# Sheet1.net
KiCad netlist of a schematic drawn in Altium Designer
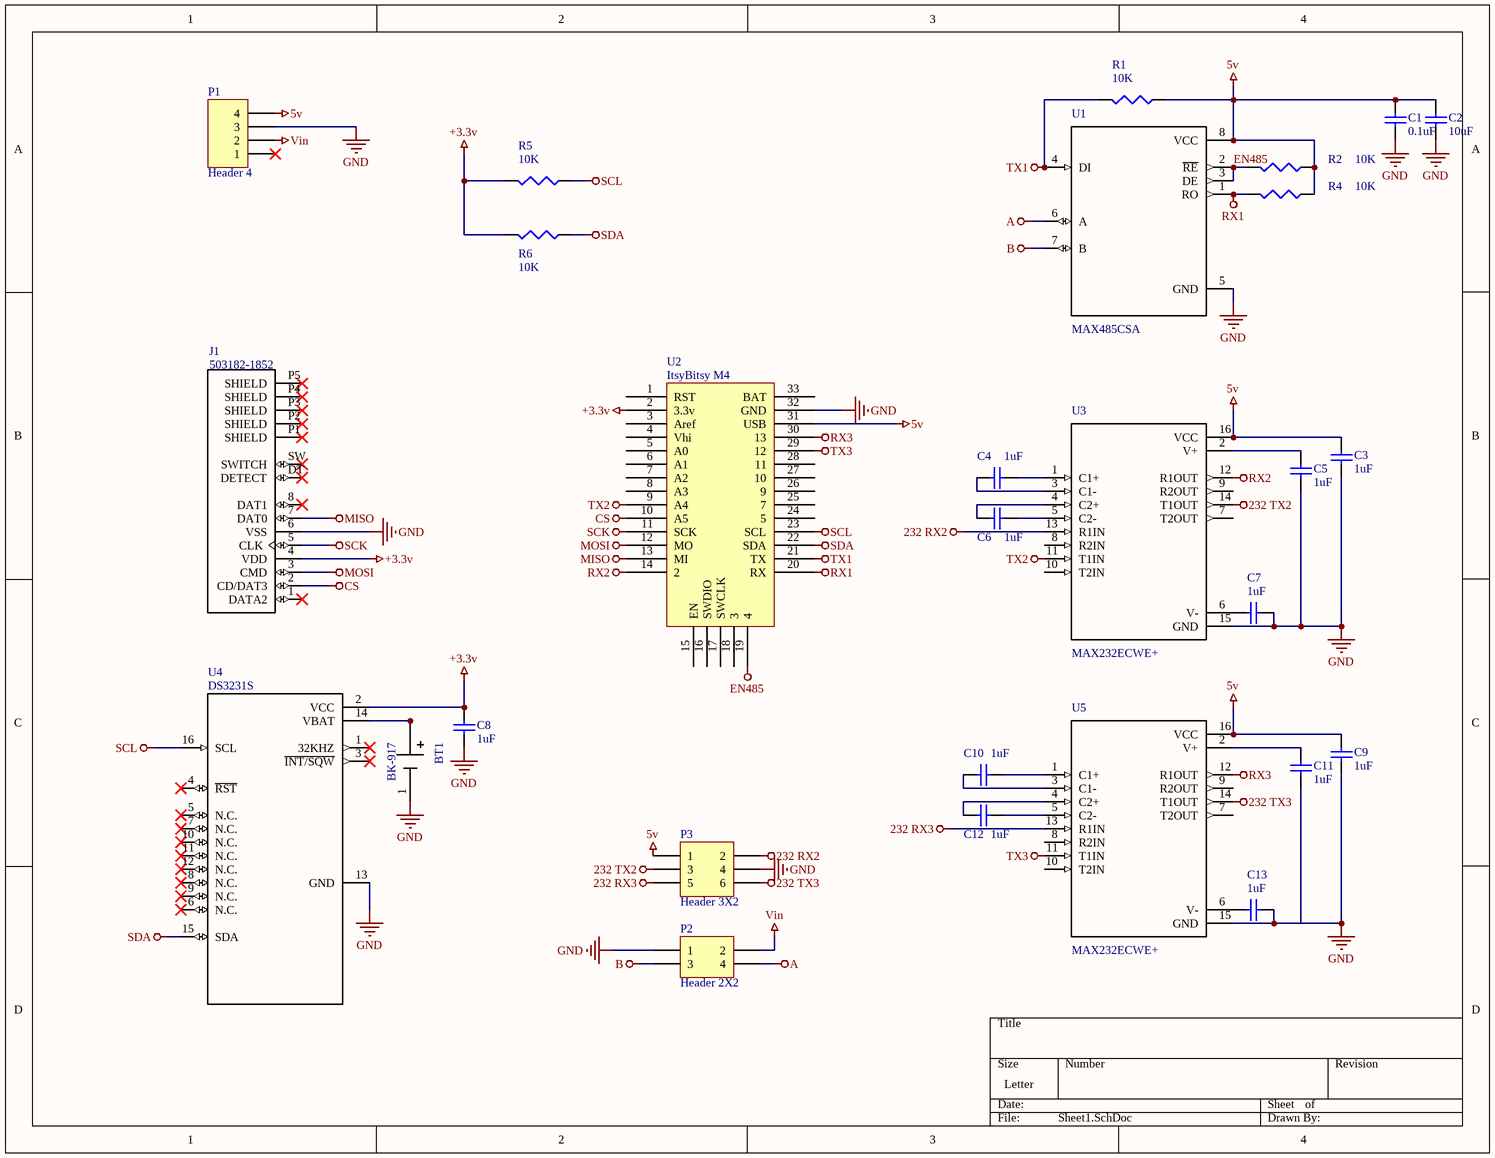
[diagram p0: Sheet1.SchDoc]

(export (version "E")
  (design (tool "Eeschema 10.0.6"))
  (components
    (comp (ref "BT1")
      (value "BK-917")
      (footprint "*BAT_BK-917_BK-917(Primary)")
      (description "BATTERY RETAINER COIN PC PIN")
      (fields (field (name "MF") "MPD"))
      (libsource (lib "BK-917") (part "BK-917"))
    )
    (comp (ref "C1")
      (value "0.1uF")
      (footprint "1608[0603]")
      (description "Capacitor (Semiconductor SIM Model)")
      (fields (field (name "Comment") "Cap Semi") (field (name "PUBLISHER") "Altium Limited"))
      (libsource (lib "Miscellaneous Devices") (part "Cap Semi"))
    )
    (comp (ref "C2")
      (value "10uF")
      (footprint "1608[0603]")
      (description "Capacitor (Semiconductor SIM Model)")
      (fields (field (name "Comment") "Cap Semi") (field (name "PUBLISHER") "Altium Limited"))
      (libsource (lib "Miscellaneous Devices") (part "Cap Semi"))
    )
    (comp (ref "C3")
      (value "1uF")
      (footprint "1608[0603]")
      (description "Capacitor (Semiconductor SIM Model)")
      (fields (field (name "Comment") "Cap Semi") (field (name "PUBLISHER") "Altium Limited"))
      (libsource (lib "Miscellaneous Devices") (part "Cap Semi"))
    )
    (comp (ref "C4")
      (value "1uF")
      (footprint "1608[0603]")
      (description "Capacitor (Semiconductor SIM Model)")
      (fields (field (name "Comment") "Cap Semi") (field (name "PUBLISHER") "Altium Limited"))
      (libsource (lib "Miscellaneous Devices") (part "Cap Semi"))
    )
    (comp (ref "C5")
      (value "1uF")
      (footprint "1608[0603]")
      (description "Capacitor (Semiconductor SIM Model)")
      (fields (field (name "Comment") "Cap Semi") (field (name "PUBLISHER") "Altium Limited"))
      (libsource (lib "Miscellaneous Devices") (part "Cap Semi"))
    )
    (comp (ref "C6")
      (value "1uF")
      (footprint "1608[0603]")
      (description "Capacitor (Semiconductor SIM Model)")
      (fields (field (name "Comment") "Cap Semi") (field (name "PUBLISHER") "Altium Limited"))
      (libsource (lib "Miscellaneous Devices") (part "Cap Semi"))
    )
    (comp (ref "C7")
      (value "1uF")
      (footprint "1608[0603]")
      (description "Capacitor (Semiconductor SIM Model)")
      (fields (field (name "Comment") "Cap Semi") (field (name "PUBLISHER") "Altium Limited"))
      (libsource (lib "Miscellaneous Devices") (part "Cap Semi"))
    )
    (comp (ref "C8")
      (value "1uF")
      (footprint "1608[0603]")
      (description "Capacitor (Semiconductor SIM Model)")
      (fields (field (name "Comment") "Cap Semi") (field (name "PUBLISHER") "Altium Limited"))
      (libsource (lib "Miscellaneous Devices") (part "Cap Semi"))
    )
    (comp (ref "C9")
      (value "1uF")
      (footprint "1608[0603]")
      (description "Capacitor (Semiconductor SIM Model)")
      (fields (field (name "Comment") "Cap Semi") (field (name "PUBLISHER") "Altium Limited"))
      (libsource (lib "Miscellaneous Devices") (part "Cap Semi"))
    )
    (comp (ref "C10")
      (value "1uF")
      (footprint "1608[0603]")
      (description "Capacitor (Semiconductor SIM Model)")
      (fields (field (name "Comment") "Cap Semi") (field (name "PUBLISHER") "Altium Limited"))
      (libsource (lib "Miscellaneous Devices") (part "Cap Semi"))
    )
    (comp (ref "C11")
      (value "1uF")
      (footprint "1608[0603]")
      (description "Capacitor (Semiconductor SIM Model)")
      (fields (field (name "Comment") "Cap Semi") (field (name "PUBLISHER") "Altium Limited"))
      (libsource (lib "Miscellaneous Devices") (part "Cap Semi"))
    )
    (comp (ref "C12")
      (value "1uF")
      (footprint "1608[0603]")
      (description "Capacitor (Semiconductor SIM Model)")
      (fields (field (name "Comment") "Cap Semi") (field (name "PUBLISHER") "Altium Limited"))
      (libsource (lib "Miscellaneous Devices") (part "Cap Semi"))
    )
    (comp (ref "C13")
      (value "1uF")
      (footprint "1608[0603]")
      (description "Capacitor (Semiconductor SIM Model)")
      (fields (field (name "Comment") "Cap Semi") (field (name "PUBLISHER") "Altium Limited"))
      (libsource (lib "Miscellaneous Devices") (part "Cap Semi"))
    )
    (comp (ref "J1")
      (value "503182-1852")
      (footprint "*MOLEX_503182-1852_503182-1852(Primary)")
      (description "MICRO SD NORMAL ULTRALOWPRO8CKTE")
      (fields (field (name "MP") "5031821852") (field (name "MF") "Molex"))
      (libsource (lib "503182-1852") (part "503182-1852"))
    )
    (comp (ref "P1")
      (value "Header 4")
      (footprint "HDR1X4")
      (description "Header, 4-Pin")
      (fields (field (name "PUBLISHER") "Altium Limited"))
      (libsource (lib "Miscellaneous Connectors") (part "Header 4"))
    )
    (comp (ref "P2")
      (value "Header 2X2")
      (footprint "2x2 MOLEX")
      (description "Header, 2-Pin, Dual row")
      (fields (field (name "PUBLISHER") "Altium Limited"))
      (libsource (lib "Miscellaneous Connectors") (part "Header 2X2"))
    )
    (comp (ref "P3")
      (value "Header 3X2")
      (footprint "2x3 MOLEX")
      (description "Header, 3-Pin, Dual row")
      (fields (field (name "PUBLISHER") "Altium Limited"))
      (libsource (lib "Miscellaneous Connectors") (part "Header 3X2"))
    )
    (comp (ref "R1")
      (value "10K")
      (footprint "J1-0603")
      (description "Resistor")
      (fields (field (name "Comment") "Res3") (field (name "PUBLISHER") "Altium Limited"))
      (libsource (lib "Miscellaneous Devices") (part "Res3"))
    )
    (comp (ref "R2")
      (value "10K")
      (footprint "J1-0603")
      (description "Resistor")
      (fields (field (name "Comment") "Res3") (field (name "PUBLISHER") "Altium Limited"))
      (libsource (lib "Miscellaneous Devices") (part "Res3"))
    )
    (comp (ref "R4")
      (value "10K")
      (footprint "J1-0603")
      (description "Resistor")
      (fields (field (name "Comment") "Res3") (field (name "PUBLISHER") "Altium Limited"))
      (libsource (lib "Miscellaneous Devices") (part "Res3"))
    )
    (comp (ref "R5")
      (value "10K")
      (footprint "J1-0603")
      (description "Resistor")
      (fields (field (name "Comment") "Res3") (field (name "PUBLISHER") "Altium Limited"))
      (libsource (lib "Miscellaneous Devices") (part "Res3"))
    )
    (comp (ref "R6")
      (value "10K")
      (footprint "J1-0603")
      (description "Resistor")
      (fields (field (name "Comment") "Res3") (field (name "PUBLISHER") "Altium Limited"))
      (libsource (lib "Miscellaneous Devices") (part "Res3"))
    )
    (comp (ref "U1")
      (value "MAX485CSA")
      (footprint "*SOIC127P600X175-8N")
      (description "1/1 Transceiver Half RS422, RS485 8-SOIC")
      (fields (field (name "MF") "Maxim Integrated"))
      (libsource (lib "MAX485CSA") (part "MAX485CSA"))
    )
    (comp (ref "U2")
      (value "ItsyBitsy M4")
      (footprint "ItsyBitsy M4")
      (libsource (lib "Schlib1") (part "ItsyBitsy M4"))
    )
    (comp (ref "U3")
      (value "MAX232ECWE+")
      (footprint "*SOIC127P1032X265-16N")
      (description "Dual Transmitter/Receiver RS-232 16-Pin SOIC W")
      (fields (field (name "MF") "Maxim Integrated"))
      (libsource (lib "MAX232ECWE_") (part "MAX232ECWE+"))
    )
    (comp (ref "U4")
      (value "DS3231S")
      (footprint "*SOIC127P1032X265-16N")
      (description "Real Time Clock Serial 16-Pin SOIC")
      (fields (field (name "MF") "Maxim Integrated"))
      (libsource (lib "DS3231S") (part "DS3231S"))
    )
    (comp (ref "U5")
      (value "MAX232ECWE+")
      (footprint "*SOIC127P1032X265-16N")
      (description "Dual Transmitter/Receiver RS-232 16-Pin SOIC W")
      (fields (field (name "MF") "Maxim Integrated"))
      (libsource (lib "MAX232ECWE_") (part "MAX232ECWE+"))
    )
  )
  (nets
    (net (code "1") (name "+3.3v") (class "Default")
      (node (ref "C8") (pin "2") (pinfunction "2_2") (pintype "passive"))
      (node (ref "J1") (pin "4") (pinfunction "VDD_4") (pintype "power_in"))
      (node (ref "R5") (pin "2") (pinfunction "2_2") (pintype "passive"))
      (node (ref "R6") (pin "2") (pinfunction "2_2") (pintype "passive"))
      (node (ref "U2") (pin "2") (pinfunction "3.3v_2") (pintype "passive"))
      (node (ref "U4") (pin "2") (pinfunction "VCC_2") (pintype "power_in"))
    )
    (net (code "2") (name "5v") (class "Default")
      (node (ref "C1") (pin "2") (pinfunction "2_2") (pintype "passive"))
      (node (ref "C2") (pin "2") (pinfunction "2_2") (pintype "passive"))
      (node (ref "C3") (pin "2") (pinfunction "2_2") (pintype "passive"))
      (node (ref "C9") (pin "2") (pinfunction "2_2") (pintype "passive"))
      (node (ref "P1") (pin "4") (pinfunction "4_4") (pintype "passive"))
      (node (ref "P3") (pin "1") (pinfunction "1_1") (pintype "passive"))
      (node (ref "R1") (pin "1") (pinfunction "1_1") (pintype "passive"))
      (node (ref "R2") (pin "1") (pinfunction "1_1") (pintype "passive"))
      (node (ref "R4") (pin "1") (pinfunction "1_1") (pintype "passive"))
      (node (ref "U1") (pin "8") (pinfunction "VCC_8") (pintype "power_in"))
      (node (ref "U2") (pin "31") (pinfunction "USB_31") (pintype "passive"))
      (node (ref "U3") (pin "16") (pinfunction "VCC_16") (pintype "power_in"))
      (node (ref "U5") (pin "16") (pinfunction "VCC_16") (pintype "power_in"))
    )
    (net (code "3") (name "232 RX2") (class "Default")
      (node (ref "P3") (pin "2") (pinfunction "2_2") (pintype "passive"))
      (node (ref "U3") (pin "13") (pinfunction "R1IN_13") (pintype "input"))
    )
    (net (code "4") (name "232 RX3") (class "Default")
      (node (ref "P3") (pin "5") (pinfunction "5_5") (pintype "passive"))
      (node (ref "U5") (pin "13") (pinfunction "R1IN_13") (pintype "input"))
    )
    (net (code "5") (name "232 TX2") (class "Default")
      (node (ref "P3") (pin "3") (pinfunction "3_3") (pintype "passive"))
      (node (ref "U3") (pin "14") (pinfunction "T1OUT_14") (pintype "output"))
    )
    (net (code "6") (name "232 TX3") (class "Default")
      (node (ref "P3") (pin "6") (pinfunction "6_6") (pintype "passive"))
      (node (ref "U5") (pin "14") (pinfunction "T1OUT_14") (pintype "output"))
    )
    (net (code "7") (name "A") (class "Default")
      (node (ref "P2") (pin "4") (pinfunction "4_4") (pintype "passive"))
      (node (ref "U1") (pin "6") (pinfunction "A_6") (pintype "bidirectional"))
    )
    (net (code "8") (name "B") (class "Default")
      (node (ref "P2") (pin "3") (pinfunction "3_3") (pintype "passive"))
      (node (ref "U1") (pin "7") (pinfunction "B_7") (pintype "bidirectional"))
    )
    (net (code "9") (name "CS") (class "Default")
      (node (ref "J1") (pin "2") (pinfunction "CD/DAT3_2") (pintype "bidirectional"))
      (node (ref "U2") (pin "10") (pinfunction "A5_10") (pintype "passive"))
    )
    (net (code "10") (name "EN485") (class "Default")
      (node (ref "R2") (pin "2") (pinfunction "2_2") (pintype "passive"))
      (node (ref "U1") (pin "2") (pinfunction "~{RE}_2") (pintype "output"))
      (node (ref "U1") (pin "3") (pinfunction "DE_3") (pintype "output"))
      (node (ref "U2") (pin "19") (pinfunction "4_19") (pintype "passive"))
    )
    (net (code "11") (name "GND") (class "Default")
      (node (ref "BT1") (pin "1") (pinfunction "NEG_1") (pintype "passive"))
      (node (ref "C1") (pin "1") (pinfunction "1_1") (pintype "passive"))
      (node (ref "C11") (pin "1") (pinfunction "1_1") (pintype "passive"))
      (node (ref "C13") (pin "1") (pinfunction "1_1") (pintype "passive"))
      (node (ref "C2") (pin "1") (pinfunction "1_1") (pintype "passive"))
      (node (ref "C3") (pin "1") (pinfunction "1_1") (pintype "passive"))
      (node (ref "C5") (pin "1") (pinfunction "1_1") (pintype "passive"))
      (node (ref "C7") (pin "1") (pinfunction "1_1") (pintype "passive"))
      (node (ref "C8") (pin "1") (pinfunction "1_1") (pintype "passive"))
      (node (ref "C9") (pin "1") (pinfunction "1_1") (pintype "passive"))
      (node (ref "J1") (pin "6") (pinfunction "VSS_6") (pintype "power_in"))
      (node (ref "P1") (pin "3") (pinfunction "3_3") (pintype "passive"))
      (node (ref "P2") (pin "1") (pinfunction "1_1") (pintype "passive"))
      (node (ref "P3") (pin "4") (pinfunction "4_4") (pintype "passive"))
      (node (ref "U1") (pin "5") (pinfunction "GND_5") (pintype "power_in"))
      (node (ref "U2") (pin "32") (pinfunction "GND_32") (pintype "passive"))
      (node (ref "U3") (pin "15") (pinfunction "GND_15") (pintype "power_in"))
      (node (ref "U4") (pin "13") (pinfunction "GND_13") (pintype "power_in"))
      (node (ref "U5") (pin "15") (pinfunction "GND_15") (pintype "power_in"))
    )
    (net (code "12") (name "MISO") (class "Default")
      (node (ref "J1") (pin "7") (pinfunction "DAT0_7") (pintype "bidirectional"))
      (node (ref "U2") (pin "13") (pinfunction "MI_13") (pintype "passive"))
    )
    (net (code "13") (name "MOSI") (class "Default")
      (node (ref "J1") (pin "3") (pinfunction "CMD_3") (pintype "bidirectional"))
      (node (ref "U2") (pin "12") (pinfunction "MO_12") (pintype "passive"))
    )
    (net (code "14") (name "Net-(U3-C1+)") (class "Default")
      (node (ref "C4") (pin "2") (pinfunction "2_2") (pintype "passive"))
      (node (ref "U3") (pin "1") (pinfunction "C1+_1") (pintype "input"))
    )
    (net (code "15") (name "Net-(U3-C1-)") (class "Default")
      (node (ref "C4") (pin "1") (pinfunction "1_1") (pintype "passive"))
      (node (ref "U3") (pin "3") (pinfunction "C1-_3") (pintype "input"))
    )
    (net (code "16") (name "Net-(U3-C2+)") (class "Default")
      (node (ref "C6") (pin "1") (pinfunction "1_1") (pintype "passive"))
      (node (ref "U3") (pin "4") (pinfunction "C2+_4") (pintype "input"))
    )
    (net (code "17") (name "Net-(U3-C2-)") (class "Default")
      (node (ref "C6") (pin "2") (pinfunction "2_2") (pintype "passive"))
      (node (ref "U3") (pin "5") (pinfunction "C2-_5") (pintype "input"))
    )
    (net (code "18") (name "Net-(U3-V+)") (class "Default")
      (node (ref "C5") (pin "2") (pinfunction "2_2") (pintype "passive"))
      (node (ref "U3") (pin "2") (pinfunction "V+_2") (pintype "power_in"))
    )
    (net (code "19") (name "Net-(U3-V-)") (class "Default")
      (node (ref "C7") (pin "2") (pinfunction "2_2") (pintype "passive"))
      (node (ref "U3") (pin "6") (pinfunction "V-_6") (pintype "power_in"))
    )
    (net (code "20") (name "Net-(U4-VBAT)") (class "Default")
      (node (ref "BT1") (pin "S1") (pinfunction "POS_S1") (pintype "passive"))
      (node (ref "BT1") (pin "S2") (pinfunction "POS_S2") (pintype "passive"))
      (node (ref "BT1") (pin "S3") (pinfunction "POS_S3") (pintype "passive"))
      (node (ref "BT1") (pin "S4") (pinfunction "POS_S4") (pintype "passive"))
      (node (ref "U4") (pin "14") (pinfunction "VBAT_14") (pintype "power_in"))
    )
    (net (code "21") (name "Net-(U5-C1+)") (class "Default")
      (node (ref "C10") (pin "2") (pinfunction "2_2") (pintype "passive"))
      (node (ref "U5") (pin "1") (pinfunction "C1+_1") (pintype "input"))
    )
    (net (code "22") (name "Net-(U5-C1-)") (class "Default")
      (node (ref "C10") (pin "1") (pinfunction "1_1") (pintype "passive"))
      (node (ref "U5") (pin "3") (pinfunction "C1-_3") (pintype "input"))
    )
    (net (code "23") (name "Net-(U5-C2+)") (class "Default")
      (node (ref "C12") (pin "1") (pinfunction "1_1") (pintype "passive"))
      (node (ref "U5") (pin "4") (pinfunction "C2+_4") (pintype "input"))
    )
    (net (code "24") (name "Net-(U5-C2-)") (class "Default")
      (node (ref "C12") (pin "2") (pinfunction "2_2") (pintype "passive"))
      (node (ref "U5") (pin "5") (pinfunction "C2-_5") (pintype "input"))
    )
    (net (code "25") (name "Net-(U5-V+)") (class "Default")
      (node (ref "C11") (pin "2") (pinfunction "2_2") (pintype "passive"))
      (node (ref "U5") (pin "2") (pinfunction "V+_2") (pintype "power_in"))
    )
    (net (code "26") (name "Net-(U5-V-)") (class "Default")
      (node (ref "C13") (pin "2") (pinfunction "2_2") (pintype "passive"))
      (node (ref "U5") (pin "6") (pinfunction "V-_6") (pintype "power_in"))
    )
    (net (code "27") (name "RX1") (class "Default")
      (node (ref "R4") (pin "2") (pinfunction "2_2") (pintype "passive"))
      (node (ref "U1") (pin "1") (pinfunction "RO_1") (pintype "output"))
      (node (ref "U2") (pin "20") (pinfunction "RX_20") (pintype "passive"))
    )
    (net (code "28") (name "RX2") (class "Default")
      (node (ref "U2") (pin "14") (pinfunction "2_14") (pintype "passive"))
      (node (ref "U3") (pin "12") (pinfunction "R1OUT_12") (pintype "output"))
    )
    (net (code "29") (name "RX3") (class "Default")
      (node (ref "U2") (pin "30") (pinfunction "13_30") (pintype "passive"))
      (node (ref "U5") (pin "12") (pinfunction "R1OUT_12") (pintype "output"))
    )
    (net (code "30") (name "SCK") (class "Default")
      (node (ref "J1") (pin "5") (pinfunction "CLK_5") (pintype "bidirectional"))
      (node (ref "U2") (pin "11") (pinfunction "SCK_11") (pintype "passive"))
    )
    (net (code "31") (name "SCL") (class "Default")
      (node (ref "R5") (pin "1") (pinfunction "1_1") (pintype "passive"))
      (node (ref "U2") (pin "23") (pinfunction "SCL_23") (pintype "passive"))
      (node (ref "U4") (pin "16") (pinfunction "SCL_16") (pintype "input"))
    )
    (net (code "32") (name "SDA") (class "Default")
      (node (ref "R6") (pin "1") (pinfunction "1_1") (pintype "passive"))
      (node (ref "U2") (pin "22") (pinfunction "SDA_22") (pintype "passive"))
      (node (ref "U4") (pin "15") (pinfunction "SDA_15") (pintype "bidirectional"))
    )
    (net (code "33") (name "TX1") (class "Default")
      (node (ref "R1") (pin "2") (pinfunction "2_2") (pintype "passive"))
      (node (ref "U1") (pin "4") (pinfunction "DI_4") (pintype "input"))
      (node (ref "U2") (pin "21") (pinfunction "TX_21") (pintype "passive"))
    )
    (net (code "34") (name "TX2") (class "Default")
      (node (ref "U2") (pin "9") (pinfunction "A4_9") (pintype "passive"))
      (node (ref "U3") (pin "11") (pinfunction "T1IN_11") (pintype "input"))
    )
    (net (code "35") (name "TX3") (class "Default")
      (node (ref "U2") (pin "29") (pinfunction "12_29") (pintype "passive"))
      (node (ref "U5") (pin "11") (pinfunction "T1IN_11") (pintype "input"))
    )
    (net (code "36") (name "Vin") (class "Default")
      (node (ref "P1") (pin "2") (pinfunction "2_2") (pintype "passive"))
      (node (ref "P2") (pin "2") (pinfunction "2_2") (pintype "passive"))
    )
    (net (code "37") (name "unconnected-(J1-DAT1-Pad8)") (class "Default")
      (node (ref "J1") (pin "8") (pinfunction "DAT1_8") (pintype "bidirectional+no_connect"))
    )
    (net (code "38") (name "unconnected-(J1-DATA2-Pad1)") (class "Default")
      (node (ref "J1") (pin "1") (pinfunction "DATA2_1") (pintype "bidirectional+no_connect"))
    )
    (net (code "39") (name "unconnected-(J1-DETECT-PadDT)") (class "Default")
      (node (ref "J1") (pin "DT") (pinfunction "DETECT_DT") (pintype "bidirectional+no_connect"))
    )
    (net (code "40") (name "unconnected-(J1-SHIELD-PadP1)") (class "Default")
      (node (ref "J1") (pin "P1") (pinfunction "SHIELD_P1") (pintype "passive+no_connect"))
    )
    (net (code "41") (name "unconnected-(J1-SHIELD-PadP2)") (class "Default")
      (node (ref "J1") (pin "P2") (pinfunction "SHIELD_P2") (pintype "passive+no_connect"))
    )
    (net (code "42") (name "unconnected-(J1-SHIELD-PadP3)") (class "Default")
      (node (ref "J1") (pin "P3") (pinfunction "SHIELD_P3") (pintype "passive+no_connect"))
    )
    (net (code "43") (name "unconnected-(J1-SHIELD-PadP4)") (class "Default")
      (node (ref "J1") (pin "P4") (pinfunction "SHIELD_P4") (pintype "passive+no_connect"))
    )
    (net (code "44") (name "unconnected-(J1-SHIELD-PadP5)") (class "Default")
      (node (ref "J1") (pin "P5") (pinfunction "SHIELD_P5") (pintype "passive+no_connect"))
    )
    (net (code "45") (name "unconnected-(J1-SWITCH-PadSW)") (class "Default")
      (node (ref "J1") (pin "SW") (pinfunction "SWITCH_SW") (pintype "bidirectional+no_connect"))
    )
    (net (code "46") (name "unconnected-(P1-Pad1)") (class "Default")
      (node (ref "P1") (pin "1") (pinfunction "1_1") (pintype "passive+no_connect"))
    )
    (net (code "47") (name "unconnected-(U2-3-Pad18)") (class "Default")
      (node (ref "U2") (pin "18") (pinfunction "3_18") (pintype "passive"))
    )
    (net (code "48") (name "unconnected-(U2-5-Pad24)") (class "Default")
      (node (ref "U2") (pin "24") (pinfunction "5_24") (pintype "passive"))
    )
    (net (code "49") (name "unconnected-(U2-7-Pad25)") (class "Default")
      (node (ref "U2") (pin "25") (pinfunction "7_25") (pintype "passive"))
    )
    (net (code "50") (name "unconnected-(U2-9-Pad26)") (class "Default")
      (node (ref "U2") (pin "26") (pinfunction "9_26") (pintype "passive"))
    )
    (net (code "51") (name "unconnected-(U2-10-Pad27)") (class "Default")
      (node (ref "U2") (pin "27") (pinfunction "10_27") (pintype "passive"))
    )
    (net (code "52") (name "unconnected-(U2-11-Pad28)") (class "Default")
      (node (ref "U2") (pin "28") (pinfunction "11_28") (pintype "passive"))
    )
    (net (code "53") (name "unconnected-(U2-A0-Pad5)") (class "Default")
      (node (ref "U2") (pin "5") (pinfunction "A0_5") (pintype "passive"))
    )
    (net (code "54") (name "unconnected-(U2-A1-Pad6)") (class "Default")
      (node (ref "U2") (pin "6") (pinfunction "A1_6") (pintype "passive"))
    )
    (net (code "55") (name "unconnected-(U2-A2-Pad7)") (class "Default")
      (node (ref "U2") (pin "7") (pinfunction "A2_7") (pintype "passive"))
    )
    (net (code "56") (name "unconnected-(U2-A3-Pad8)") (class "Default")
      (node (ref "U2") (pin "8") (pinfunction "A3_8") (pintype "passive"))
    )
    (net (code "57") (name "unconnected-(U2-Aref-Pad3)") (class "Default")
      (node (ref "U2") (pin "3") (pinfunction "Aref_3") (pintype "passive"))
    )
    (net (code "58") (name "unconnected-(U2-BAT-Pad33)") (class "Default")
      (node (ref "U2") (pin "33") (pinfunction "BAT_33") (pintype "passive"))
    )
    (net (code "59") (name "unconnected-(U2-EN-Pad15)") (class "Default")
      (node (ref "U2") (pin "15") (pinfunction "EN_15") (pintype "passive"))
    )
    (net (code "60") (name "unconnected-(U2-RST-Pad1)") (class "Default")
      (node (ref "U2") (pin "1") (pinfunction "RST_1") (pintype "passive"))
    )
    (net (code "61") (name "unconnected-(U2-SWCLK-Pad17)") (class "Default")
      (node (ref "U2") (pin "17") (pinfunction "SWCLK_17") (pintype "passive"))
    )
    (net (code "62") (name "unconnected-(U2-SWDIO-Pad16)") (class "Default")
      (node (ref "U2") (pin "16") (pinfunction "SWDIO_16") (pintype "passive"))
    )
    (net (code "63") (name "unconnected-(U2-Vhi-Pad4)") (class "Default")
      (node (ref "U2") (pin "4") (pinfunction "Vhi_4") (pintype "passive"))
    )
    (net (code "64") (name "unconnected-(U3-R2IN-Pad8)") (class "Default")
      (node (ref "U3") (pin "8") (pinfunction "R2IN_8") (pintype "input"))
    )
    (net (code "65") (name "unconnected-(U3-R2OUT-Pad9)") (class "Default")
      (node (ref "U3") (pin "9") (pinfunction "R2OUT_9") (pintype "output"))
    )
    (net (code "66") (name "unconnected-(U3-T2IN-Pad10)") (class "Default")
      (node (ref "U3") (pin "10") (pinfunction "T2IN_10") (pintype "input"))
    )
    (net (code "67") (name "unconnected-(U3-T2OUT-Pad7)") (class "Default")
      (node (ref "U3") (pin "7") (pinfunction "T2OUT_7") (pintype "output"))
    )
    (net (code "68") (name "unconnected-(U4-32KHZ-Pad1)") (class "Default")
      (node (ref "U4") (pin "1") (pinfunction "32KHZ_1") (pintype "output+no_connect"))
    )
    (net (code "69") (name "unconnected-(U4-N.C.-Pad5)") (class "Default")
      (node (ref "U4") (pin "5") (pinfunction "N.C._5") (pintype "bidirectional+no_connect"))
    )
    (net (code "70") (name "unconnected-(U4-N.C.-Pad6)") (class "Default")
      (node (ref "U4") (pin "6") (pinfunction "N.C._6") (pintype "bidirectional+no_connect"))
    )
    (net (code "71") (name "unconnected-(U4-N.C.-Pad7)") (class "Default")
      (node (ref "U4") (pin "7") (pinfunction "N.C._7") (pintype "bidirectional+no_connect"))
    )
    (net (code "72") (name "unconnected-(U4-N.C.-Pad8)") (class "Default")
      (node (ref "U4") (pin "8") (pinfunction "N.C._8") (pintype "bidirectional+no_connect"))
    )
    (net (code "73") (name "unconnected-(U4-N.C.-Pad9)") (class "Default")
      (node (ref "U4") (pin "9") (pinfunction "N.C._9") (pintype "bidirectional+no_connect"))
    )
    (net (code "74") (name "unconnected-(U4-N.C.-Pad10)") (class "Default")
      (node (ref "U4") (pin "10") (pinfunction "N.C._10") (pintype "bidirectional+no_connect"))
    )
    (net (code "75") (name "unconnected-(U4-N.C.-Pad11)") (class "Default")
      (node (ref "U4") (pin "11") (pinfunction "N.C._11") (pintype "bidirectional+no_connect"))
    )
    (net (code "76") (name "unconnected-(U4-N.C.-Pad12)") (class "Default")
      (node (ref "U4") (pin "12") (pinfunction "N.C._12") (pintype "bidirectional+no_connect"))
    )
    (net (code "77") (name "unconnected-(U4-~{INT{slash}SQW}-Pad3)") (class "Default")
      (node (ref "U4") (pin "3") (pinfunction "~{INT/SQW}_3") (pintype "output+no_connect"))
    )
    (net (code "78") (name "unconnected-(U4-~{RST}-Pad4)") (class "Default")
      (node (ref "U4") (pin "4") (pinfunction "~{RST}_4") (pintype "bidirectional+no_connect"))
    )
    (net (code "79") (name "unconnected-(U5-R2IN-Pad8)") (class "Default")
      (node (ref "U5") (pin "8") (pinfunction "R2IN_8") (pintype "input"))
    )
    (net (code "80") (name "unconnected-(U5-R2OUT-Pad9)") (class "Default")
      (node (ref "U5") (pin "9") (pinfunction "R2OUT_9") (pintype "output"))
    )
    (net (code "81") (name "unconnected-(U5-T2IN-Pad10)") (class "Default")
      (node (ref "U5") (pin "10") (pinfunction "T2IN_10") (pintype "input"))
    )
    (net (code "82") (name "unconnected-(U5-T2OUT-Pad7)") (class "Default")
      (node (ref "U5") (pin "7") (pinfunction "T2OUT_7") (pintype "output"))
    )
  )
)
